# Sheet1.net
KiCad netlist of a schematic drawn in Altium Designer
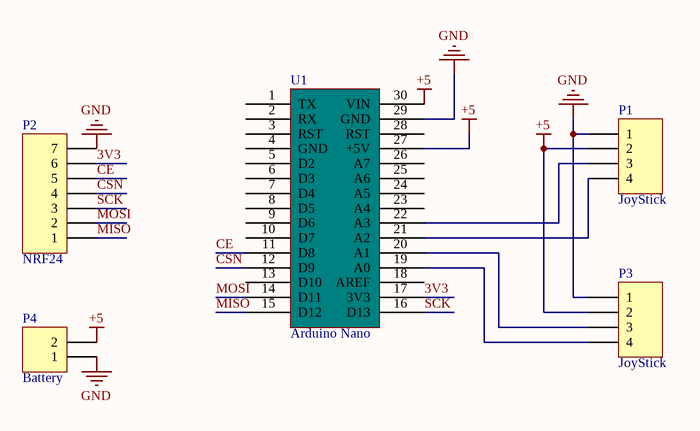
[diagram p0: Sheet1.SchDoc]

(export (version "E")
  (design (tool "Eeschema 10.0.6"))
  (components
    (comp (ref "P1")
      (value "JoyStick")
      (footprint "HDR1X4")
      (description "Header, 4-Pin")
      (fields (field (name "PUBLISHER") "Altium Limited"))
      (libsource (lib "Miscellaneous Connectors") (part "Header 4"))
    )
    (comp (ref "P2")
      (value "NRF24")
      (footprint "HDR1X7")
      (description "Header, 7-Pin")
      (fields (field (name "PUBLISHER") "Altium Limited"))
      (libsource (lib "Miscellaneous Connectors") (part "Header 7"))
    )
    (comp (ref "P3")
      (value "JoyStick")
      (footprint "HDR1X4")
      (description "Header, 4-Pin")
      (fields (field (name "PUBLISHER") "Altium Limited"))
      (libsource (lib "Miscellaneous Connectors") (part "Header 4"))
    )
    (comp (ref "P4")
      (value "Battery")
      (footprint "HDR1X2")
      (description "Header, 2-Pin")
      (fields (field (name "PUBLISHER") "Altium Limited"))
      (libsource (lib "Miscellaneous Connectors") (part "Header 2"))
    )
    (comp (ref "U1")
      (value "Arduino Nano")
      (footprint "PCBComponent_1")
      (libsource (lib "Nano") (part "Component_1"))
    )
  )
  (nets
    (net (code "1") (name "+5") (class "Default")
      (node (ref "P1") (pin "2") (pinfunction "2_2") (pintype "passive"))
      (node (ref "P3") (pin "2") (pinfunction "2_2") (pintype "passive"))
      (node (ref "P4") (pin "2") (pinfunction "2_2") (pintype "passive"))
      (node (ref "U1") (pin "27") (pinfunction "+5V_27") (pintype "passive"))
      (node (ref "U1") (pin "30") (pinfunction "VIN_30") (pintype "passive"))
    )
    (net (code "2") (name "/3V3") (class "Default")
      (node (ref "P2") (pin "6") (pinfunction "6_6") (pintype "passive"))
      (node (ref "U1") (pin "17") (pinfunction "3V3_17") (pintype "passive"))
    )
    (net (code "3") (name "/CE") (class "Default")
      (node (ref "P2") (pin "5") (pinfunction "5_5") (pintype "passive"))
      (node (ref "U1") (pin "11") (pinfunction "D8_11") (pintype "passive"))
    )
    (net (code "4") (name "/CSN") (class "Default")
      (node (ref "P2") (pin "4") (pinfunction "4_4") (pintype "passive"))
      (node (ref "U1") (pin "12") (pinfunction "D9_12") (pintype "passive"))
    )
    (net (code "5") (name "/MISO") (class "Default")
      (node (ref "P2") (pin "1") (pinfunction "1_1") (pintype "passive"))
      (node (ref "U1") (pin "15") (pinfunction "D12_15") (pintype "passive"))
    )
    (net (code "6") (name "/MOSI") (class "Default")
      (node (ref "P2") (pin "2") (pinfunction "2_2") (pintype "passive"))
      (node (ref "U1") (pin "14") (pinfunction "D11_14") (pintype "passive"))
    )
    (net (code "7") (name "/SCK") (class "Default")
      (node (ref "P2") (pin "3") (pinfunction "3_3") (pintype "passive"))
      (node (ref "U1") (pin "16") (pinfunction "D13_16") (pintype "passive"))
    )
    (net (code "8") (name "GND") (class "Default")
      (node (ref "P1") (pin "1") (pinfunction "1_1") (pintype "passive"))
      (node (ref "P2") (pin "7") (pinfunction "7_7") (pintype "passive"))
      (node (ref "P3") (pin "1") (pinfunction "1_1") (pintype "passive"))
      (node (ref "P4") (pin "1") (pinfunction "1_1") (pintype "passive"))
      (node (ref "U1") (pin "29") (pinfunction "GND_29") (pintype "passive"))
    )
    (net (code "9") (name "Net-(U1-A0)") (class "Default")
      (node (ref "P3") (pin "4") (pinfunction "4_4") (pintype "passive"))
      (node (ref "U1") (pin "19") (pinfunction "A0_19") (pintype "passive"))
    )
    (net (code "10") (name "Net-(U1-A1)") (class "Default")
      (node (ref "P3") (pin "3") (pinfunction "3_3") (pintype "passive"))
      (node (ref "U1") (pin "20") (pinfunction "A1_20") (pintype "passive"))
    )
    (net (code "11") (name "Net-(U1-A2)") (class "Default")
      (node (ref "P1") (pin "4") (pinfunction "4_4") (pintype "passive"))
      (node (ref "U1") (pin "21") (pinfunction "A2_21") (pintype "passive"))
    )
    (net (code "12") (name "Net-(U1-A3)") (class "Default")
      (node (ref "P1") (pin "3") (pinfunction "3_3") (pintype "passive"))
      (node (ref "U1") (pin "22") (pinfunction "A3_22") (pintype "passive"))
    )
    (net (code "13") (name "unconnected-(U1-A4-Pad23)") (class "Default")
      (node (ref "U1") (pin "23") (pinfunction "A4_23") (pintype "passive"))
    )
    (net (code "14") (name "unconnected-(U1-A5-Pad24)") (class "Default")
      (node (ref "U1") (pin "24") (pinfunction "A5_24") (pintype "passive"))
    )
    (net (code "15") (name "unconnected-(U1-A6-Pad25)") (class "Default")
      (node (ref "U1") (pin "25") (pinfunction "A6_25") (pintype "passive"))
    )
    (net (code "16") (name "unconnected-(U1-A7-Pad26)") (class "Default")
      (node (ref "U1") (pin "26") (pinfunction "A7_26") (pintype "passive"))
    )
    (net (code "17") (name "unconnected-(U1-AREF-Pad18)") (class "Default")
      (node (ref "U1") (pin "18") (pinfunction "AREF_18") (pintype "passive"))
    )
    (net (code "18") (name "unconnected-(U1-D2-Pad5)") (class "Default")
      (node (ref "U1") (pin "5") (pinfunction "D2_5") (pintype "passive"))
    )
    (net (code "19") (name "unconnected-(U1-D3-Pad6)") (class "Default")
      (node (ref "U1") (pin "6") (pinfunction "D3_6") (pintype "passive"))
    )
    (net (code "20") (name "unconnected-(U1-D4-Pad7)") (class "Default")
      (node (ref "U1") (pin "7") (pinfunction "D4_7") (pintype "passive"))
    )
    (net (code "21") (name "unconnected-(U1-D5-Pad8)") (class "Default")
      (node (ref "U1") (pin "8") (pinfunction "D5_8") (pintype "passive"))
    )
    (net (code "22") (name "unconnected-(U1-D6-Pad9)") (class "Default")
      (node (ref "U1") (pin "9") (pinfunction "D6_9") (pintype "passive"))
    )
    (net (code "23") (name "unconnected-(U1-D7-Pad10)") (class "Default")
      (node (ref "U1") (pin "10") (pinfunction "D7_10") (pintype "passive"))
    )
    (net (code "24") (name "unconnected-(U1-D10-Pad13)") (class "Default")
      (node (ref "U1") (pin "13") (pinfunction "D10_13") (pintype "passive"))
    )
    (net (code "25") (name "unconnected-(U1-GND-Pad4)") (class "Default")
      (node (ref "U1") (pin "4") (pinfunction "GND_4") (pintype "passive"))
    )
    (net (code "26") (name "unconnected-(U1-RST-Pad3)") (class "Default")
      (node (ref "U1") (pin "3") (pinfunction "RST_3") (pintype "passive"))
    )
    (net (code "27") (name "unconnected-(U1-RST-Pad28)") (class "Default")
      (node (ref "U1") (pin "28") (pinfunction "RST_28") (pintype "passive"))
    )
    (net (code "28") (name "unconnected-(U1-RX-Pad2)") (class "Default")
      (node (ref "U1") (pin "2") (pinfunction "RX_2") (pintype "passive"))
    )
    (net (code "29") (name "unconnected-(U1-TX-Pad1)") (class "Default")
      (node (ref "U1") (pin "1") (pinfunction "TX_1") (pintype "passive"))
    )
  )
)
